# stand.net
KiCad netlist of a schematic drawn in EAGLE
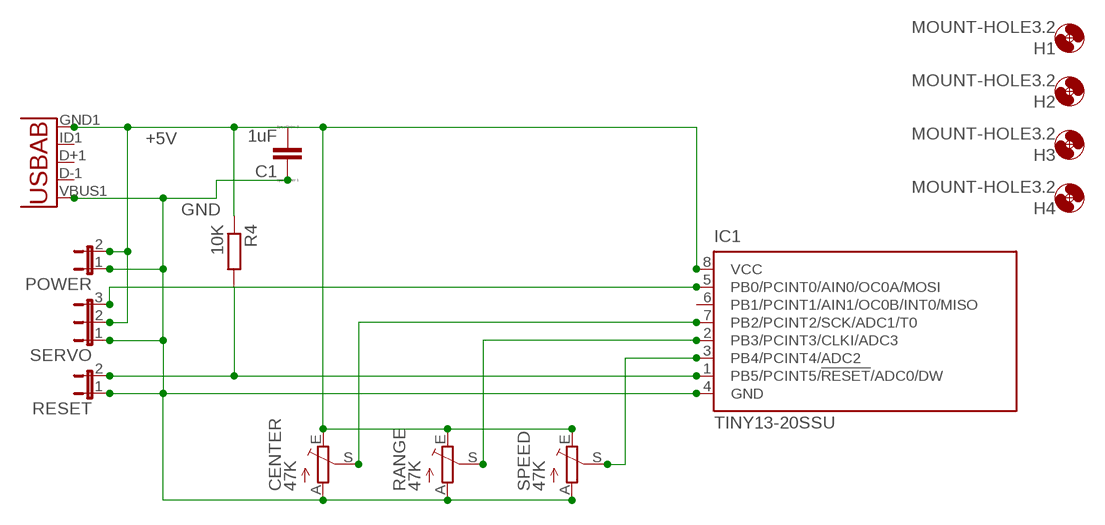
[diagram p0: schematic, sheet 1]

(export (version "E")
  (design (tool "Eeschema 10.0.6"))
  (components
    (comp (ref "C1")
      (value "1uF")
      (footprint "eagle-import:C0805")
      (libsource (lib "eagle-import") (part "C"))
    )
    (comp (ref "CENTER")
      (value "47K")
      (footprint "eagle-import:RJ6S")
      (libsource (lib "eagle-import") (part "TRIM_EU-RJ6S"))
    )
    (comp (ref "H1")
      (value "MOUNT-HOLE3.2")
      (footprint "eagle-import:3,2")
      (libsource (lib "eagle-import") (part "MOUNT-HOLE3.2"))
    )
    (comp (ref "H2")
      (value "MOUNT-HOLE3.2")
      (footprint "eagle-import:3,2")
      (libsource (lib "eagle-import") (part "MOUNT-HOLE3.2"))
    )
    (comp (ref "H3")
      (value "MOUNT-HOLE3.2")
      (footprint "eagle-import:3,2")
      (libsource (lib "eagle-import") (part "MOUNT-HOLE3.2"))
    )
    (comp (ref "H4")
      (value "MOUNT-HOLE3.2")
      (footprint "eagle-import:3,2")
      (libsource (lib "eagle-import") (part "MOUNT-HOLE3.2"))
    )
    (comp (ref "IC1")
      (value "TINY13-20SSU")
      (footprint "eagle-import:8S1")
      (fields (field (name "MPN") "ATTINY13-20SSU"))
      (libsource (lib "eagle-import") (part "TINY13SSU-20"))
    )
    (comp (ref "POWER")
      (value "JP1E")
      (footprint "eagle-import:JP1")
      (libsource (lib "eagle-import") (part "JP1E"))
    )
    (comp (ref "R4")
      (value "10K")
      (footprint "eagle-import:M0805")
      (libsource (lib "eagle-import") (part "R-EU_M0805"))
    )
    (comp (ref "RANGE")
      (value "47K")
      (footprint "eagle-import:RJ6S")
      (libsource (lib "eagle-import") (part "TRIM_EU-RJ6S"))
    )
    (comp (ref "RESET")
      (value "JP1E")
      (footprint "eagle-import:JP1")
      (libsource (lib "eagle-import") (part "JP1E"))
    )
    (comp (ref "SERVO")
      (value "JP2E")
      (footprint "eagle-import:JP2")
      (libsource (lib "eagle-import") (part "JP2E"))
    )
    (comp (ref "SPEED")
      (value "47K")
      (footprint "eagle-import:RJ6S")
      (libsource (lib "eagle-import") (part "TRIM_EU-RJ6S"))
    )
    (comp (ref "U$1")
      (value "USB\"\"")
      (footprint "eagle-import:USB-MICRO-SMD")
      (libsource (lib "eagle-import") (part "USB{dblquote}{dblquote}"))
    )
  )
  (nets
    (net (code "1") (name "/+5V") (class "Default")
      (node (ref "C1") (pin "2") (pinfunction "2_2") (pintype "passive"))
      (node (ref "CENTER") (pin "E") (pinfunction "E_E") (pintype "passive"))
      (node (ref "IC1") (pin "8") (pinfunction "VCC_8") (pintype "power_in"))
      (node (ref "POWER") (pin "2") (pinfunction "2_2") (pintype "passive"))
      (node (ref "R4") (pin "1") (pinfunction "1_1") (pintype "passive"))
      (node (ref "RANGE") (pin "E") (pinfunction "E_E") (pintype "passive"))
      (node (ref "SERVO") (pin "2") (pinfunction "2_2") (pintype "passive"))
      (node (ref "SPEED") (pin "E") (pinfunction "E_E") (pintype "passive"))
      (node (ref "U$1") (pin "GND1") (pinfunction "GND_GND1") (pintype "bidirectional"))
    )
    (net (code "2") (name "/GND") (class "Default")
      (node (ref "C1") (pin "1") (pinfunction "1_1") (pintype "passive"))
      (node (ref "CENTER") (pin "A") (pinfunction "A_A") (pintype "passive"))
      (node (ref "IC1") (pin "4") (pinfunction "GND_4") (pintype "power_in"))
      (node (ref "POWER") (pin "1") (pinfunction "1_1") (pintype "passive"))
      (node (ref "RANGE") (pin "A") (pinfunction "A_A") (pintype "passive"))
      (node (ref "RESET") (pin "1") (pinfunction "1_1") (pintype "passive"))
      (node (ref "SERVO") (pin "1") (pinfunction "1_1") (pintype "passive"))
      (node (ref "SPEED") (pin "A") (pinfunction "A_A") (pintype "passive"))
      (node (ref "U$1") (pin "VBUS1") (pinfunction "VBUS_VBUS1") (pintype "bidirectional"))
    )
    (net (code "3") (name "Net-(IC1-PB0{slash}PCINT0{slash}AIN0{slash}OC0A{slash}MOSI)") (class "Default")
      (node (ref "IC1") (pin "5") (pinfunction "PB0/PCINT0/AIN0/OC0A/MOSI_5") (pintype "bidirectional"))
      (node (ref "SERVO") (pin "3") (pinfunction "3_3") (pintype "passive"))
    )
    (net (code "4") (name "Net-(IC1-PB2{slash}PCINT2{slash}SCK{slash}ADC1{slash}T0)") (class "Default")
      (node (ref "CENTER") (pin "S") (pinfunction "S_S") (pintype "passive"))
      (node (ref "IC1") (pin "7") (pinfunction "PB2/PCINT2/SCK/ADC1/T0_7") (pintype "bidirectional"))
    )
    (net (code "5") (name "Net-(IC1-PB3{slash}PCINT3{slash}CLKI{slash}ADC3)") (class "Default")
      (node (ref "IC1") (pin "2") (pinfunction "PB3/PCINT3/CLKI/ADC3_2") (pintype "bidirectional"))
      (node (ref "RANGE") (pin "S") (pinfunction "S_S") (pintype "passive"))
    )
    (net (code "6") (name "Net-(IC1-PB4{slash}PCINT4{slash}ADC2)") (class "Default")
      (node (ref "IC1") (pin "3") (pinfunction "PB4/PCINT4/ADC2_3") (pintype "bidirectional"))
      (node (ref "SPEED") (pin "S") (pinfunction "S_S") (pintype "passive"))
    )
    (net (code "7") (name "Net-(IC1-PB5{slash}PCINT5{slash}~{RESET}{slash}ADC0{slash}DW)") (class "Default")
      (node (ref "IC1") (pin "1") (pinfunction "PB5/PCINT5/~{RESET}/ADC0/DW_1") (pintype "bidirectional"))
      (node (ref "R4") (pin "2") (pinfunction "2_2") (pintype "passive"))
      (node (ref "RESET") (pin "2") (pinfunction "2_2") (pintype "passive"))
    )
    (net (code "8") (name "unconnected-(IC1-PB1{slash}PCINT1{slash}AIN1{slash}OC0B{slash}INT0{slash}MISO-Pad6)") (class "Default")
      (node (ref "IC1") (pin "6") (pinfunction "PB1/PCINT1/AIN1/OC0B/INT0/MISO_6") (pintype "bidirectional"))
    )
    (net (code "9") (name "unconnected-(U$1-D+-PadD+1)") (class "Default")
      (node (ref "U$1") (pin "D+1") (pinfunction "D+_D+1") (pintype "bidirectional"))
    )
    (net (code "10") (name "unconnected-(U$1-D--PadD-1)") (class "Default")
      (node (ref "U$1") (pin "D-1") (pinfunction "D-_D-1") (pintype "bidirectional"))
    )
    (net (code "11") (name "unconnected-(U$1-USBID-PadID1)") (class "Default")
      (node (ref "U$1") (pin "ID1") (pinfunction "USBID_ID1") (pintype "bidirectional"))
    )
  )
)
